# sdb.net
KiCad netlist of a schematic drawn in Altium Designer
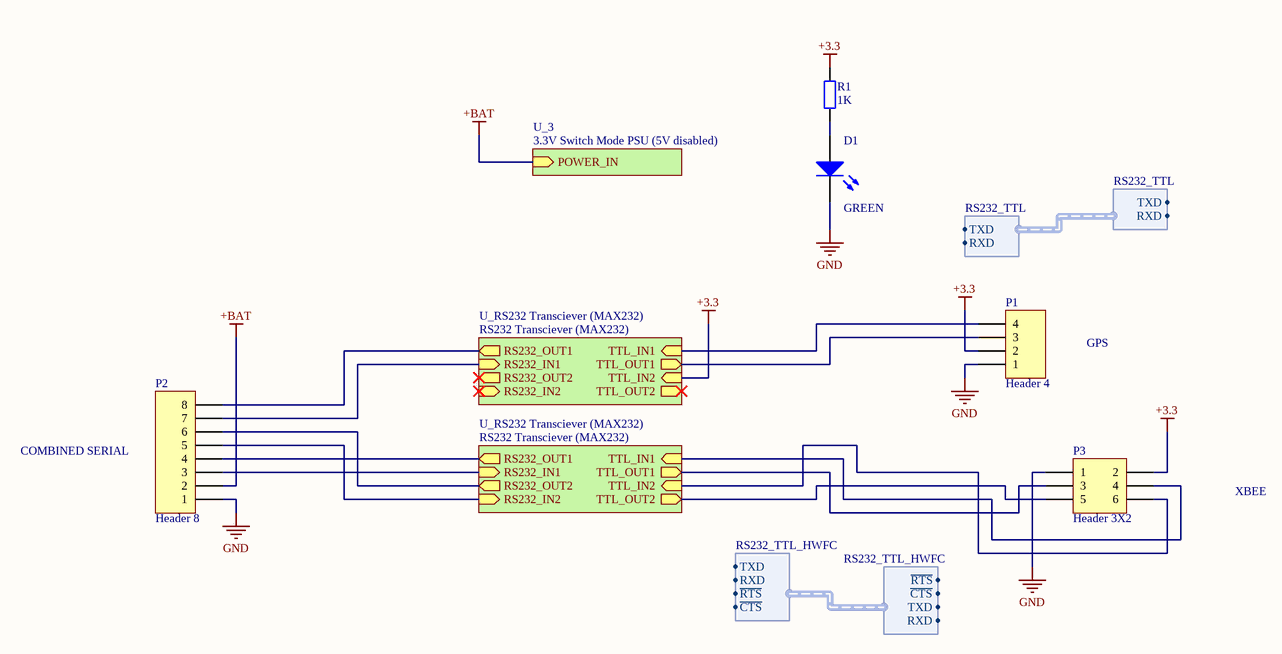
[diagram p0: sdb.SchDoc]

(export (version "E")
  (design (tool "Eeschema 10.0.6"))
  (components
    (comp (ref "D1")
      (value "GREEN")
      (footprint "LGQ971")
      (description "Typical RED, GREEN, YELLOW, AMBER GaAs LED")
      (libsource (lib "Miscellaneous Devices") (part "LED2"))
    )
    (comp (ref "P1")
      (value "Header 4")
      (footprint "HDR1X4")
      (description "Header, 4-Pin")
      (fields (field (name "PUBLISHER") "Altium Limited"))
      (libsource (lib "Miscellaneous Connectors") (part "Header 4"))
    )
    (comp (ref "P2")
      (value "Header 8")
      (footprint "HDR1X8")
      (description "Header, 8-Pin")
      (fields (field (name "PUBLISHER") "Altium Limited"))
      (libsource (lib "Miscellaneous Connectors") (part "Header 8"))
    )
    (comp (ref "P3")
      (value "Header 3X2")
      (footprint "HDR2X3")
      (description "Header, 3-Pin, Dual row")
      (fields (field (name "PUBLISHER") "Altium Limited"))
      (libsource (lib "Miscellaneous Connectors") (part "Header 3X2"))
    )
    (comp (ref "R1")
      (value "1K")
      (footprint "R0603")
      (description "Resistor")
      (fields (field (name "Comment") "Res"))
      (libsource (lib "Miscellaneous Devices") (part "Res2"))
    )
  )
  (nets
    (net (code "3") (name "+3.3") (class "Default")
      (node (ref "P1") (pin "2") (pinfunction "2_2") (pintype "passive"))
      (node (ref "P3") (pin "2") (pinfunction "2_2") (pintype "passive"))
      (node (ref "R1") (pin "2") (pinfunction "2_2") (pintype "passive"))
    )
    (net (code "4") (name "+BAT") (class "Default")
      (node (ref "P2") (pin "2") (pinfunction "2_2") (pintype "passive"))
    )
    (net (code "5") (name "/RS232_IN1") (class "Default")
      (node (ref "P2") (pin "7") (pinfunction "7_7") (pintype "passive"))
    )
    (net (code "6") (name "/RS232_IN1_1") (class "Default")
      (node (ref "P2") (pin "3") (pinfunction "3_3") (pintype "passive"))
    )
    (net (code "8") (name "/RS232_IN2_1") (class "Default")
      (node (ref "P2") (pin "5") (pinfunction "5_5") (pintype "passive"))
    )
    (net (code "9") (name "/RS232_OUT1") (class "Default")
      (node (ref "P2") (pin "8") (pinfunction "8_8") (pintype "passive"))
    )
    (net (code "10") (name "/RS232_OUT1_1") (class "Default")
      (node (ref "P2") (pin "4") (pinfunction "4_4") (pintype "passive"))
    )
    (net (code "12") (name "/RS232_OUT2_1") (class "Default")
      (node (ref "P2") (pin "6") (pinfunction "6_6") (pintype "passive"))
    )
    (net (code "13") (name "/TTL_IN1") (class "Default")
      (node (ref "P3") (pin "4") (pinfunction "4_4") (pintype "passive"))
    )
    (net (code "14") (name "/TTL_IN1_1") (class "Default")
      (node (ref "P1") (pin "4") (pinfunction "4_4") (pintype "passive"))
    )
    (net (code "15") (name "/TTL_IN2") (class "Default")
      (node (ref "P3") (pin "6") (pinfunction "6_6") (pintype "passive"))
    )
    (net (code "16") (name "/TTL_OUT1") (class "Default")
      (node (ref "P3") (pin "3") (pinfunction "3_3") (pintype "passive"))
    )
    (net (code "17") (name "/TTL_OUT1_1") (class "Default")
      (node (ref "P1") (pin "3") (pinfunction "3_3") (pintype "passive"))
    )
    (net (code "18") (name "/TTL_OUT2") (class "Default")
      (node (ref "P3") (pin "5") (pinfunction "5_5") (pintype "passive"))
    )
    (net (code "22") (name "GND") (class "Default")
      (node (ref "D1") (pin "2") (pinfunction "K_2") (pintype "passive"))
      (node (ref "P1") (pin "1") (pinfunction "1_1") (pintype "passive"))
      (node (ref "P2") (pin "1") (pinfunction "1_1") (pintype "passive"))
      (node (ref "P3") (pin "1") (pinfunction "1_1") (pintype "passive"))
    )
    (net (code "23") (name "Net-(D1-A)") (class "Default")
      (node (ref "D1") (pin "1") (pinfunction "A_1") (pintype "passive"))
      (node (ref "R1") (pin "1") (pinfunction "1_1") (pintype "passive"))
    )
  )
)
